# COMMINACATION.net
KiCad netlist of a schematic drawn in Altium Designer
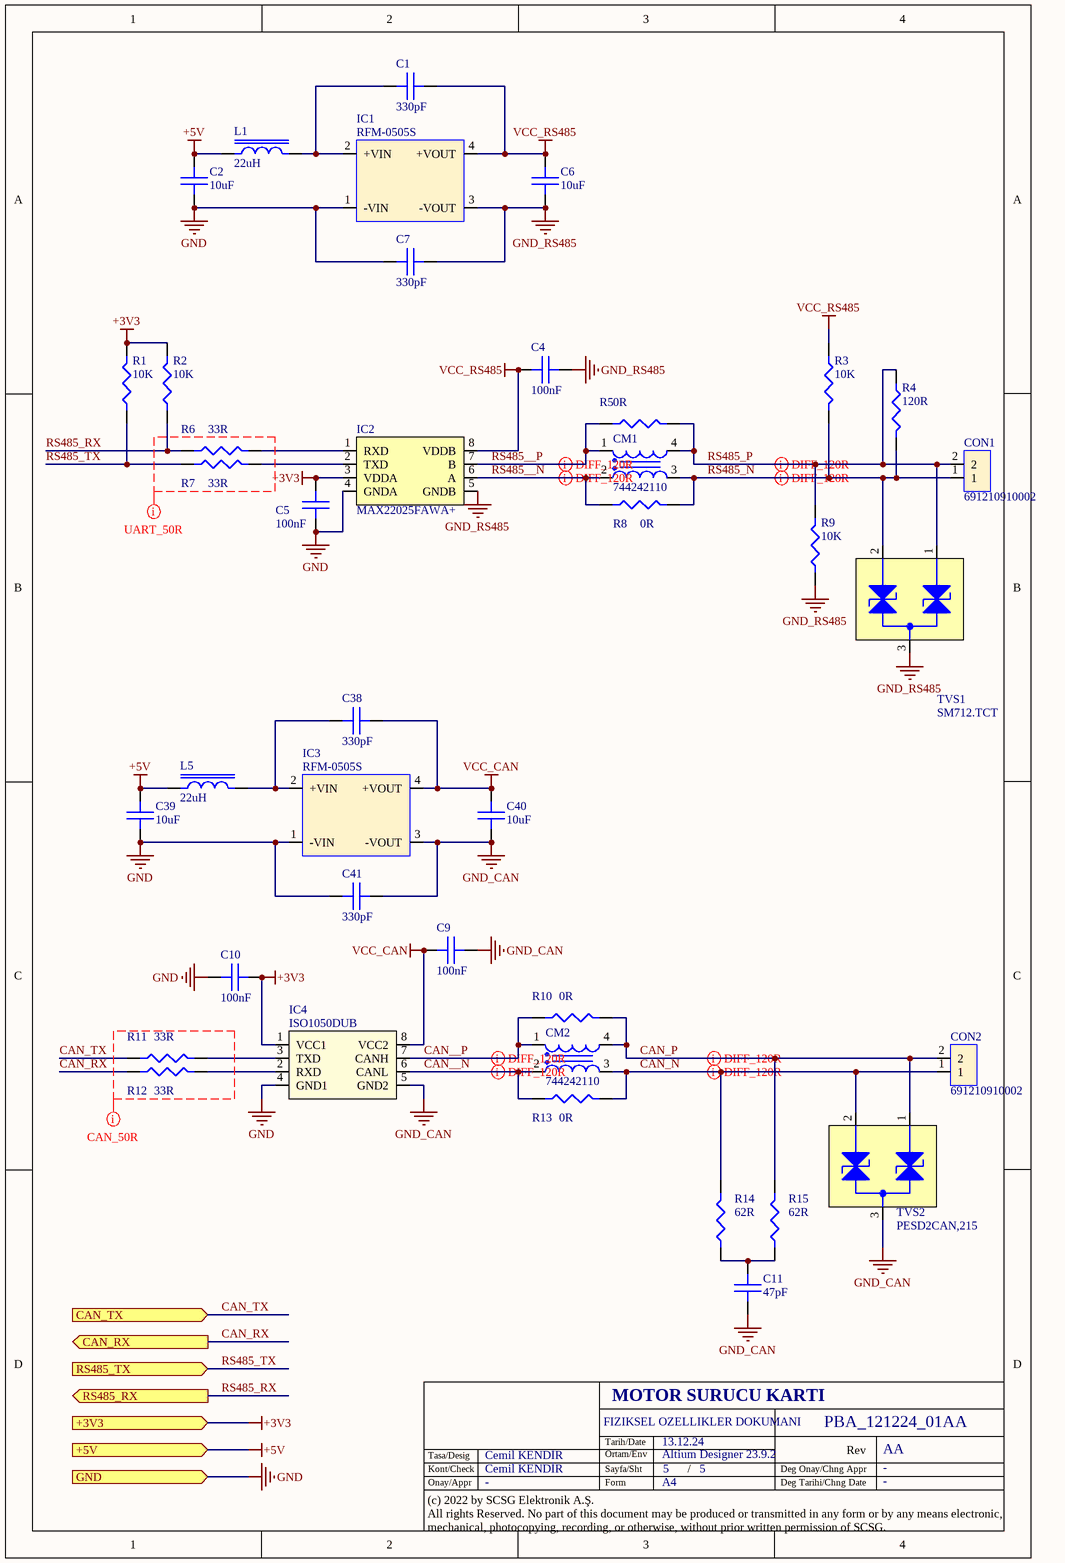
[diagram p0: COMMINACATION.SchDoc]

(export (version "E")
  (design (tool "Eeschema 10.0.6"))
  (components
    (comp (ref "C1")
      (value "330pF")
      (footprint "C1206")
      (description "330pF, 1000V,  C0G, 1206")
      (fields
        (field (name "MANUFACTURER") "Yageo")
        (field (name "MANUFACTURER PART NUMBER") "CC1206JKNPOCBN331")
      )
      (libsource (lib "Capacitor") (part "CC1206JKNPOCBN331"))
    )
    (comp (ref "C2")
      (value "10uF")
      (footprint "C0402")
      (description "10uF, 6.3V, X5R, 0402")
      (fields
        (field (name "MANUFACTURER") "Murata")
        (field (name "MANUFACTURER PART NUMBER") "GRM155R60J106ME15D")
      )
      (libsource (lib "Capacitor") (part "GRM155R60J106ME15D"))
    )
    (comp (ref "C4")
      (value "100nF")
      (footprint "C0402")
      (description "100nF ,10V ,X7R ,0402")
      (fields
        (field (name "MANUFACTURER") "Yageo")
        (field (name "MANUFACTURER PART NUMBER") "CC0402KRX7R6BB104")
      )
      (libsource (lib "Capacitor") (part "CC0402KRX7R6BB104"))
    )
    (comp (ref "C5")
      (value "100nF")
      (footprint "C0402")
      (description "100nF ,10V ,X7R ,0402")
      (fields
        (field (name "MANUFACTURER") "Yageo")
        (field (name "MANUFACTURER PART NUMBER") "CC0402KRX7R6BB104")
      )
      (libsource (lib "Capacitor") (part "CC0402KRX7R6BB104"))
    )
    (comp (ref "C6")
      (value "10uF")
      (footprint "C0402")
      (description "10uF, 6.3V, X5R, 0402")
      (fields
        (field (name "MANUFACTURER") "Murata")
        (field (name "MANUFACTURER PART NUMBER") "GRM155R60J106ME15D")
      )
      (libsource (lib "Capacitor") (part "GRM155R60J106ME15D"))
    )
    (comp (ref "C7")
      (value "330pF")
      (footprint "C1206")
      (description "330pF, 1000V,  C0G, 1206")
      (fields
        (field (name "MANUFACTURER") "Yageo")
        (field (name "MANUFACTURER PART NUMBER") "CC1206JKNPOCBN331")
      )
      (libsource (lib "Capacitor") (part "CC1206JKNPOCBN331"))
    )
    (comp (ref "C9")
      (value "100nF")
      (footprint "C0402")
      (description "100nF ,10V ,X7R ,0402")
      (fields
        (field (name "MANUFACTURER") "Yageo")
        (field (name "MANUFACTURER PART NUMBER") "CC0402KRX7R6BB104")
      )
      (libsource (lib "Capacitor") (part "CC0402KRX7R6BB104"))
    )
    (comp (ref "C10")
      (value "100nF")
      (footprint "C0402")
      (description "100nF ,10V ,X7R ,0402")
      (fields
        (field (name "MANUFACTURER") "Yageo")
        (field (name "MANUFACTURER PART NUMBER") "CC0402KRX7R6BB104")
      )
      (libsource (lib "Capacitor") (part "CC0402KRX7R6BB104"))
    )
    (comp (ref "C11")
      (value "47pF")
      (footprint "C0402")
      (description "47pF, 50V, NP0, 0402")
      (fields
        (field (name "MANUFACTURER") "Yageo")
        (field (name "MANUFACTURER PART NUMBER") "CC0402JRNPO9BN470")
      )
      (libsource (lib "Capacitor") (part "CC0402JRNPO9BN470"))
    )
    (comp (ref "C38")
      (value "330pF")
      (footprint "C1206")
      (description "330pF, 1000V,  C0G, 1206")
      (fields
        (field (name "MANUFACTURER") "Yageo")
        (field (name "MANUFACTURER PART NUMBER") "CC1206JKNPOCBN331")
      )
      (libsource (lib "Capacitor") (part "CC1206JKNPOCBN331"))
    )
    (comp (ref "C39")
      (value "10uF")
      (footprint "C0402")
      (description "10uF, 6.3V, X5R, 0402")
      (fields
        (field (name "MANUFACTURER") "Murata")
        (field (name "MANUFACTURER PART NUMBER") "GRM155R60J106ME15D")
      )
      (libsource (lib "Capacitor") (part "GRM155R60J106ME15D"))
    )
    (comp (ref "C40")
      (value "10uF")
      (footprint "C0402")
      (description "10uF, 6.3V, X5R, 0402")
      (fields
        (field (name "MANUFACTURER") "Murata")
        (field (name "MANUFACTURER PART NUMBER") "GRM155R60J106ME15D")
      )
      (libsource (lib "Capacitor") (part "GRM155R60J106ME15D"))
    )
    (comp (ref "C41")
      (value "330pF")
      (footprint "C1206")
      (description "330pF, 1000V,  C0G, 1206")
      (fields
        (field (name "MANUFACTURER") "Yageo")
        (field (name "MANUFACTURER PART NUMBER") "CC1206JKNPOCBN331")
      )
      (libsource (lib "Capacitor") (part "CC1206JKNPOCBN331"))
    )
    (comp (ref "CM1")
      (value "744242110")
      (footprint "WE-SLM_L6W3.3H3.3")
      (description "Data Line Filter, 2 Function(s), 80V, 0.3A, 4 Pin(s)")
      (fields (field (name "MANUFACTURER") "Wurth Electronics"))
      (libsource (lib "Protection") (part "744242110"))
    )
    (comp (ref "CM2")
      (value "744242110")
      (footprint "WE-SLM_L6W3.3H3.3")
      (description "Data Line Filter, 2 Function(s), 80V, 0.3A, 4 Pin(s)")
      (fields (field (name "MANUFACTURER") "Wurth Electronics"))
      (libsource (lib "Protection") (part "744242110"))
    )
    (comp (ref "CON1")
      (value "691210910002")
      (footprint "691210910002")
      (description "2.54 Mm Terminal Block, Horizont")
      (fields (field (name "MANUFACTURER") "Wurth Electronics"))
      (libsource (lib "Connectors") (part "691210910002"))
    )
    (comp (ref "CON2")
      (value "691210910002")
      (footprint "691210910002")
      (description "2.54 Mm Terminal Block, Horizont")
      (fields (field (name "MANUFACTURER") "Wurth Electronics"))
      (libsource (lib "Connectors") (part "691210910002"))
    )
    (comp (ref "IC1")
      (value "RFM-0505S")
      (footprint "RFM-0505S")
      (fields (field (name "MANUFACTURER") "Recom"))
      (libsource (lib "Moduls") (part "RFM-0505S"))
    )
    (comp (ref "IC2")
      (value "MAX22025FAWA+")
      (footprint "WIDE SOIC 08")
      (description "IC Transceiver Half 1/1 8SOIC")
      (fields (field (name "MANUFACTURER") "Analog Devices"))
      (libsource (lib "IntegratedCircuit") (part "MAX22025FAWA+"))
    )
    (comp (ref "IC3")
      (value "RFM-0505S")
      (footprint "RFM-0505S")
      (fields (field (name "MANUFACTURER") "Recom"))
      (libsource (lib "Moduls") (part "RFM-0505S"))
    )
    (comp (ref "IC4")
      (value "ISO1050DUB")
      (footprint "SOP254P1040X485-8N")
      (description "EAR99 ISO1050 Tube CANbus interface transceiver 5V 73mA 850.995985mg 74ns")
      (fields (field (name "MANUFACTURER") "Texas Instruments"))
      (libsource (lib "IntegratedCircuit") (part "ISO1050DUB"))
    )
    (comp (ref "L1")
      (value "22uH")
      (footprint "WE-LQ_1210")
      (description "General Purpose Inductor, 22uH, 10%, 1 Element, Ferrite-Core, SMD, 1210")
      (fields
        (field (name "MANUFACTURER") "Wurth Electronics")
        (field (name "MANUFACTURER PART NUMBER") "744032220")
      )
      (libsource (lib "Inductor") (part "744032220"))
    )
    (comp (ref "L5")
      (value "22uH")
      (footprint "WE-LQ_1210")
      (description "General Purpose Inductor, 22uH, 10%, 1 Element, Ferrite-Core, SMD, 1210")
      (fields
        (field (name "MANUFACTURER") "Wurth Electronics")
        (field (name "MANUFACTURER PART NUMBER") "744032220")
      )
      (libsource (lib "Inductor") (part "744032220"))
    )
    (comp (ref "R1")
      (value "10K")
      (footprint "R0402")
      (description "10K, %1, 1/16W, 0402")
      (fields
        (field (name "MANUFACTURER") "YAGEO")
        (field (name "MANUFACTURER PART NUMBER") "RC0402FR-0710KL")
      )
      (libsource (lib "Resistor") (part "RC0402FR-0710KL"))
    )
    (comp (ref "R2")
      (value "10K")
      (footprint "R0402")
      (description "10K, %1, 1/16W, 0402")
      (fields
        (field (name "MANUFACTURER") "YAGEO")
        (field (name "MANUFACTURER PART NUMBER") "RC0402FR-0710KL")
      )
      (libsource (lib "Resistor") (part "RC0402FR-0710KL"))
    )
    (comp (ref "R3")
      (value "10K")
      (footprint "R0402")
      (description "10K, %1, 1/16W, 0402")
      (fields
        (field (name "MANUFACTURER") "YAGEO")
        (field (name "MANUFACTURER PART NUMBER") "RC0402FR-0710KL")
      )
      (libsource (lib "Resistor") (part "RC0402FR-0710KL"))
    )
    (comp (ref "R4")
      (value "120R")
      (footprint "R0603")
      (description "120R ,%1 ,1/10 W ,0603")
      (fields
        (field (name "MANUFACTURER") "YAGEO")
        (field (name "MANUFACTURER PART NUMBER") "RC0603FR-07120RL")
      )
      (libsource (lib "Resistor") (part "RC0603FR-07120RL"))
    )
    (comp (ref "R5")
      (value "0R")
      (footprint "R0402")
      (description "0R, %1, 1/10W,  0402")
      (fields
        (field (name "MANUFACTURER") "YAGEO")
        (field (name "MANUFACTURER PART NUMBER") "RC0402FR-070RL")
      )
      (libsource (lib "Resistor") (part "RC0402FR-070RL"))
    )
    (comp (ref "R6")
      (value "33R")
      (footprint "R0402")
      (description "33R, %5, 1/16W ,0402")
      (fields
        (field (name "MANUFACTURER") "YAGEO")
        (field (name "MANUFACTURER PART NUMBER") "RC0402JR-0733RL")
      )
      (libsource (lib "Resistor") (part "RC0402JR-0733RL"))
    )
    (comp (ref "R7")
      (value "33R")
      (footprint "R0402")
      (description "33R, %5, 1/16W ,0402")
      (fields
        (field (name "MANUFACTURER") "YAGEO")
        (field (name "MANUFACTURER PART NUMBER") "RC0402JR-0733RL")
      )
      (libsource (lib "Resistor") (part "RC0402JR-0733RL"))
    )
    (comp (ref "R8")
      (value "0R")
      (footprint "R0402")
      (description "0R, %1, 1/10W,  0402")
      (fields
        (field (name "MANUFACTURER") "YAGEO")
        (field (name "MANUFACTURER PART NUMBER") "RC0402FR-070RL")
      )
      (libsource (lib "Resistor") (part "RC0402FR-070RL"))
    )
    (comp (ref "R9")
      (value "10K")
      (footprint "R0402")
      (description "10K, %1, 1/16W, 0402")
      (fields
        (field (name "MANUFACTURER") "YAGEO")
        (field (name "MANUFACTURER PART NUMBER") "RC0402FR-0710KL")
      )
      (libsource (lib "Resistor") (part "RC0402FR-0710KL"))
    )
    (comp (ref "R10")
      (value "0R")
      (footprint "R0402")
      (description "0R, %1, 1/10W,  0402")
      (fields
        (field (name "MANUFACTURER") "YAGEO")
        (field (name "MANUFACTURER PART NUMBER") "RC0402FR-070RL")
      )
      (libsource (lib "Resistor") (part "RC0402FR-070RL"))
    )
    (comp (ref "R11")
      (value "33R")
      (footprint "R0402")
      (description "33R, %5, 1/16W ,0402")
      (fields
        (field (name "MANUFACTURER") "YAGEO")
        (field (name "MANUFACTURER PART NUMBER") "RC0402JR-0733RL")
      )
      (libsource (lib "Resistor") (part "RC0402JR-0733RL"))
    )
    (comp (ref "R12")
      (value "33R")
      (footprint "R0402")
      (description "33R, %5, 1/16W ,0402")
      (fields
        (field (name "MANUFACTURER") "YAGEO")
        (field (name "MANUFACTURER PART NUMBER") "RC0402JR-0733RL")
      )
      (libsource (lib "Resistor") (part "RC0402JR-0733RL"))
    )
    (comp (ref "R13")
      (value "0R")
      (footprint "R0402")
      (description "0R, %1, 1/10W,  0402")
      (fields
        (field (name "MANUFACTURER") "YAGEO")
        (field (name "MANUFACTURER PART NUMBER") "RC0402FR-070RL")
      )
      (libsource (lib "Resistor") (part "RC0402FR-070RL"))
    )
    (comp (ref "R14")
      (value "62R")
      (footprint "R0805")
      (description "62R, %5, 1/8W, 0805")
      (fields
        (field (name "MANUFACTURER") "YAGEO")
        (field (name "MANUFACTURER PART NUMBER") "RC0805JR-0762RL")
      )
      (libsource (lib "Resistor") (part "RC0805JR-0762RL"))
    )
    (comp (ref "R15")
      (value "62R")
      (footprint "R0805")
      (description "62R, %5, 1/8W, 0805")
      (fields
        (field (name "MANUFACTURER") "YAGEO")
        (field (name "MANUFACTURER PART NUMBER") "RC0805JR-0762RL")
      )
      (libsource (lib "Resistor") (part "RC0805JR-0762RL"))
    )
    (comp (ref "TVS1")
      (value "SM712.TCT")
      (footprint "WE-TVS_SOT23-3L")
      (description "SM Series 12 V 400 W Asymmetrical TVS Diode for Extended Common-Mode - SOT-23")
      (fields (field (name "MANUFACTURER") "Semtech"))
      (libsource (lib "Protection") (part "SM712.TCT"))
    )
    (comp (ref "TVS2")
      (value "PESD2CAN,215")
      (footprint "WE-TVS_SOT23-3L")
      (description "PESD Series 2 Channel Bi-Directional CAN Bus ESD Protection Diode - SOT-23")
      (fields (field (name "MANUFACTURER") "Nexperia USA"))
      (libsource (lib "Protection") (part "PESD2CAN,215"))
    )
  )
  (nets
    (net (code "1") (name "+3V3") (class "Default")
      (node (ref "C10") (pin "2") (pintype "passive"))
      (node (ref "C5") (pin "2") (pintype "passive"))
      (node (ref "IC2") (pin "3") (pinfunction "VDDA_3") (pintype "passive"))
      (node (ref "IC4") (pin "1") (pinfunction "VCC1_1") (pintype "passive"))
      (node (ref "R1") (pin "2") (pinfunction "2_2") (pintype "passive"))
      (node (ref "R2") (pin "2") (pinfunction "2_2") (pintype "passive"))
    )
    (net (code "2") (name "+5V") (class "Default")
      (node (ref "C2") (pin "2") (pintype "passive"))
      (node (ref "C39") (pin "2") (pintype "passive"))
      (node (ref "L1") (pin "1") (pinfunction "1_1") (pintype "passive"))
      (node (ref "L5") (pin "1") (pinfunction "1_1") (pintype "passive"))
    )
    (net (code "3") (name "/CAN_N") (class "Default")
      (node (ref "CM2") (pin "3") (pinfunction "3_3") (pintype "passive"))
      (node (ref "CON2") (pin "1") (pinfunction "1_1") (pintype "passive"))
      (node (ref "R13") (pin "2") (pinfunction "2_2") (pintype "passive"))
      (node (ref "R14") (pin "2") (pinfunction "2_2") (pintype "passive"))
      (node (ref "TVS2") (pin "2") (pinfunction "I/O_2_2") (pintype "passive"))
    )
    (net (code "4") (name "/CAN_P") (class "Default")
      (node (ref "CM2") (pin "4") (pinfunction "4_4") (pintype "passive"))
      (node (ref "CON2") (pin "2") (pinfunction "2_2") (pintype "passive"))
      (node (ref "R10") (pin "2") (pinfunction "2_2") (pintype "passive"))
      (node (ref "R15") (pin "2") (pinfunction "2_2") (pintype "passive"))
      (node (ref "TVS2") (pin "1") (pinfunction "I/O_1_1") (pintype "passive"))
    )
    (net (code "5") (name "/CAN_RX") (class "Default")
      (node (ref "R12") (pin "1") (pinfunction "1_1") (pintype "passive"))
    )
    (net (code "6") (name "/CAN_TX") (class "Default")
      (node (ref "R11") (pin "1") (pinfunction "1_1") (pintype "passive"))
    )
    (net (code "7") (name "/CAN__N") (class "Default")
      (node (ref "CM2") (pin "2") (pinfunction "2_2") (pintype "passive"))
      (node (ref "IC4") (pin "6") (pinfunction "CANL_6") (pintype "passive"))
      (node (ref "R13") (pin "1") (pinfunction "1_1") (pintype "passive"))
    )
    (net (code "8") (name "/CAN__P") (class "Default")
      (node (ref "CM2") (pin "1") (pinfunction "1_1") (pintype "passive"))
      (node (ref "IC4") (pin "7") (pinfunction "CANH_7") (pintype "passive"))
      (node (ref "R10") (pin "1") (pinfunction "1_1") (pintype "passive"))
    )
    (net (code "9") (name "/RS485_N") (class "Default")
      (node (ref "CM1") (pin "3") (pinfunction "3_3") (pintype "passive"))
      (node (ref "CON1") (pin "1") (pinfunction "1_1") (pintype "passive"))
      (node (ref "R3") (pin "2") (pinfunction "2_2") (pintype "passive"))
      (node (ref "R4") (pin "2") (pinfunction "2_2") (pintype "passive"))
      (node (ref "R8") (pin "2") (pinfunction "2_2") (pintype "passive"))
      (node (ref "TVS1") (pin "2") (pinfunction "I/O_2_2") (pintype "passive"))
    )
    (net (code "10") (name "/RS485_P") (class "Default")
      (node (ref "CM1") (pin "4") (pinfunction "4_4") (pintype "passive"))
      (node (ref "CON1") (pin "2") (pinfunction "2_2") (pintype "passive"))
      (node (ref "R4") (pin "1") (pinfunction "1_1") (pintype "passive"))
      (node (ref "R5") (pin "2") (pinfunction "2_2") (pintype "passive"))
      (node (ref "R9") (pin "2") (pinfunction "2_2") (pintype "passive"))
      (node (ref "TVS1") (pin "1") (pinfunction "I/O_1_1") (pintype "passive"))
    )
    (net (code "11") (name "/RS485_RX") (class "Default")
      (node (ref "R2") (pin "1") (pinfunction "1_1") (pintype "passive"))
      (node (ref "R6") (pin "1") (pinfunction "1_1") (pintype "passive"))
    )
    (net (code "12") (name "/RS485_TX") (class "Default")
      (node (ref "R1") (pin "1") (pinfunction "1_1") (pintype "passive"))
      (node (ref "R7") (pin "1") (pinfunction "1_1") (pintype "passive"))
    )
    (net (code "13") (name "/RS485__N") (class "Default")
      (node (ref "CM1") (pin "2") (pinfunction "2_2") (pintype "passive"))
      (node (ref "IC2") (pin "6") (pinfunction "A_6") (pintype "passive"))
      (node (ref "R8") (pin "1") (pinfunction "1_1") (pintype "passive"))
    )
    (net (code "14") (name "/RS485__P") (class "Default")
      (node (ref "CM1") (pin "1") (pinfunction "1_1") (pintype "passive"))
      (node (ref "IC2") (pin "7") (pinfunction "B_7") (pintype "passive"))
      (node (ref "R5") (pin "1") (pinfunction "1_1") (pintype "passive"))
    )
    (net (code "15") (name "GND") (class "Default")
      (node (ref "C10") (pin "1") (pintype "passive"))
      (node (ref "C2") (pin "1") (pintype "passive"))
      (node (ref "C39") (pin "1") (pintype "passive"))
      (node (ref "C41") (pin "1") (pintype "passive"))
      (node (ref "C5") (pin "1") (pintype "passive"))
      (node (ref "C7") (pin "1") (pintype "passive"))
      (node (ref "IC1") (pin "1") (pinfunction "-VIN_1") (pintype "passive"))
      (node (ref "IC2") (pin "4") (pinfunction "GNDA_4") (pintype "passive"))
      (node (ref "IC3") (pin "1") (pinfunction "-VIN_1") (pintype "passive"))
      (node (ref "IC4") (pin "4") (pinfunction "GND1_4") (pintype "passive"))
    )
    (net (code "16") (name "GND_CAN") (class "Default")
      (node (ref "C11") (pin "1") (pintype "passive"))
      (node (ref "C40") (pin "1") (pintype "passive"))
      (node (ref "C41") (pin "2") (pintype "passive"))
      (node (ref "C9") (pin "1") (pintype "passive"))
      (node (ref "IC3") (pin "3") (pinfunction "-VOUT_3") (pintype "passive"))
      (node (ref "IC4") (pin "5") (pinfunction "GND2_5") (pintype "passive"))
      (node (ref "TVS2") (pin "3") (pinfunction "GND_3") (pintype "passive"))
    )
    (net (code "17") (name "GND_RS485") (class "Default")
      (node (ref "C4") (pin "1") (pintype "passive"))
      (node (ref "C6") (pin "1") (pintype "passive"))
      (node (ref "C7") (pin "2") (pintype "passive"))
      (node (ref "IC1") (pin "3") (pinfunction "-VOUT_3") (pintype "passive"))
      (node (ref "IC2") (pin "5") (pinfunction "GNDB_5") (pintype "passive"))
      (node (ref "R9") (pin "1") (pinfunction "1_1") (pintype "passive"))
      (node (ref "TVS1") (pin "3") (pinfunction "GND_3") (pintype "passive"))
    )
    (net (code "18") (name "Net-(C11-Pad2)") (class "Default")
      (node (ref "C11") (pin "2") (pintype "passive"))
      (node (ref "R14") (pin "1") (pinfunction "1_1") (pintype "passive"))
      (node (ref "R15") (pin "1") (pinfunction "1_1") (pintype "passive"))
    )
    (net (code "19") (name "Net-(IC1-+VIN)") (class "Default")
      (node (ref "C1") (pin "1") (pintype "passive"))
      (node (ref "IC1") (pin "2") (pinfunction "+VIN_2") (pintype "passive"))
      (node (ref "L1") (pin "2") (pinfunction "2_2") (pintype "passive"))
    )
    (net (code "20") (name "Net-(IC2-RXD)") (class "Default")
      (node (ref "IC2") (pin "1") (pinfunction "RXD_1") (pintype "passive"))
      (node (ref "R6") (pin "2") (pinfunction "2_2") (pintype "passive"))
    )
    (net (code "21") (name "Net-(IC2-TXD)") (class "Default")
      (node (ref "IC2") (pin "2") (pinfunction "TXD_2") (pintype "passive"))
      (node (ref "R7") (pin "2") (pinfunction "2_2") (pintype "passive"))
    )
    (net (code "22") (name "Net-(IC3-+VIN)") (class "Default")
      (node (ref "C38") (pin "1") (pintype "passive"))
      (node (ref "IC3") (pin "2") (pinfunction "+VIN_2") (pintype "passive"))
      (node (ref "L5") (pin "2") (pinfunction "2_2") (pintype "passive"))
    )
    (net (code "23") (name "Net-(IC4-RXD)") (class "Default")
      (node (ref "IC4") (pin "2") (pinfunction "RXD_2") (pintype "passive"))
      (node (ref "R12") (pin "2") (pinfunction "2_2") (pintype "passive"))
    )
    (net (code "24") (name "Net-(IC4-TXD)") (class "Default")
      (node (ref "IC4") (pin "3") (pinfunction "TXD_3") (pintype "passive"))
      (node (ref "R11") (pin "2") (pinfunction "2_2") (pintype "passive"))
    )
    (net (code "25") (name "VCC_CAN") (class "Default")
      (node (ref "C38") (pin "2") (pintype "passive"))
      (node (ref "C40") (pin "2") (pintype "passive"))
      (node (ref "C9") (pin "2") (pintype "passive"))
      (node (ref "IC3") (pin "4") (pinfunction "+VOUT_4") (pintype "passive"))
      (node (ref "IC4") (pin "8") (pinfunction "VCC2_8") (pintype "passive"))
    )
    (net (code "26") (name "VCC_RS485") (class "Default")
      (node (ref "C1") (pin "2") (pintype "passive"))
      (node (ref "C4") (pin "2") (pintype "passive"))
      (node (ref "C6") (pin "2") (pintype "passive"))
      (node (ref "IC1") (pin "4") (pinfunction "+VOUT_4") (pintype "passive"))
      (node (ref "IC2") (pin "8") (pinfunction "VDDB_8") (pintype "passive"))
      (node (ref "R3") (pin "1") (pinfunction "1_1") (pintype "passive"))
    )
  )
)
